# AE_ESP_mnt_board.net
KiCad netlist of a schematic drawn in EAGLE
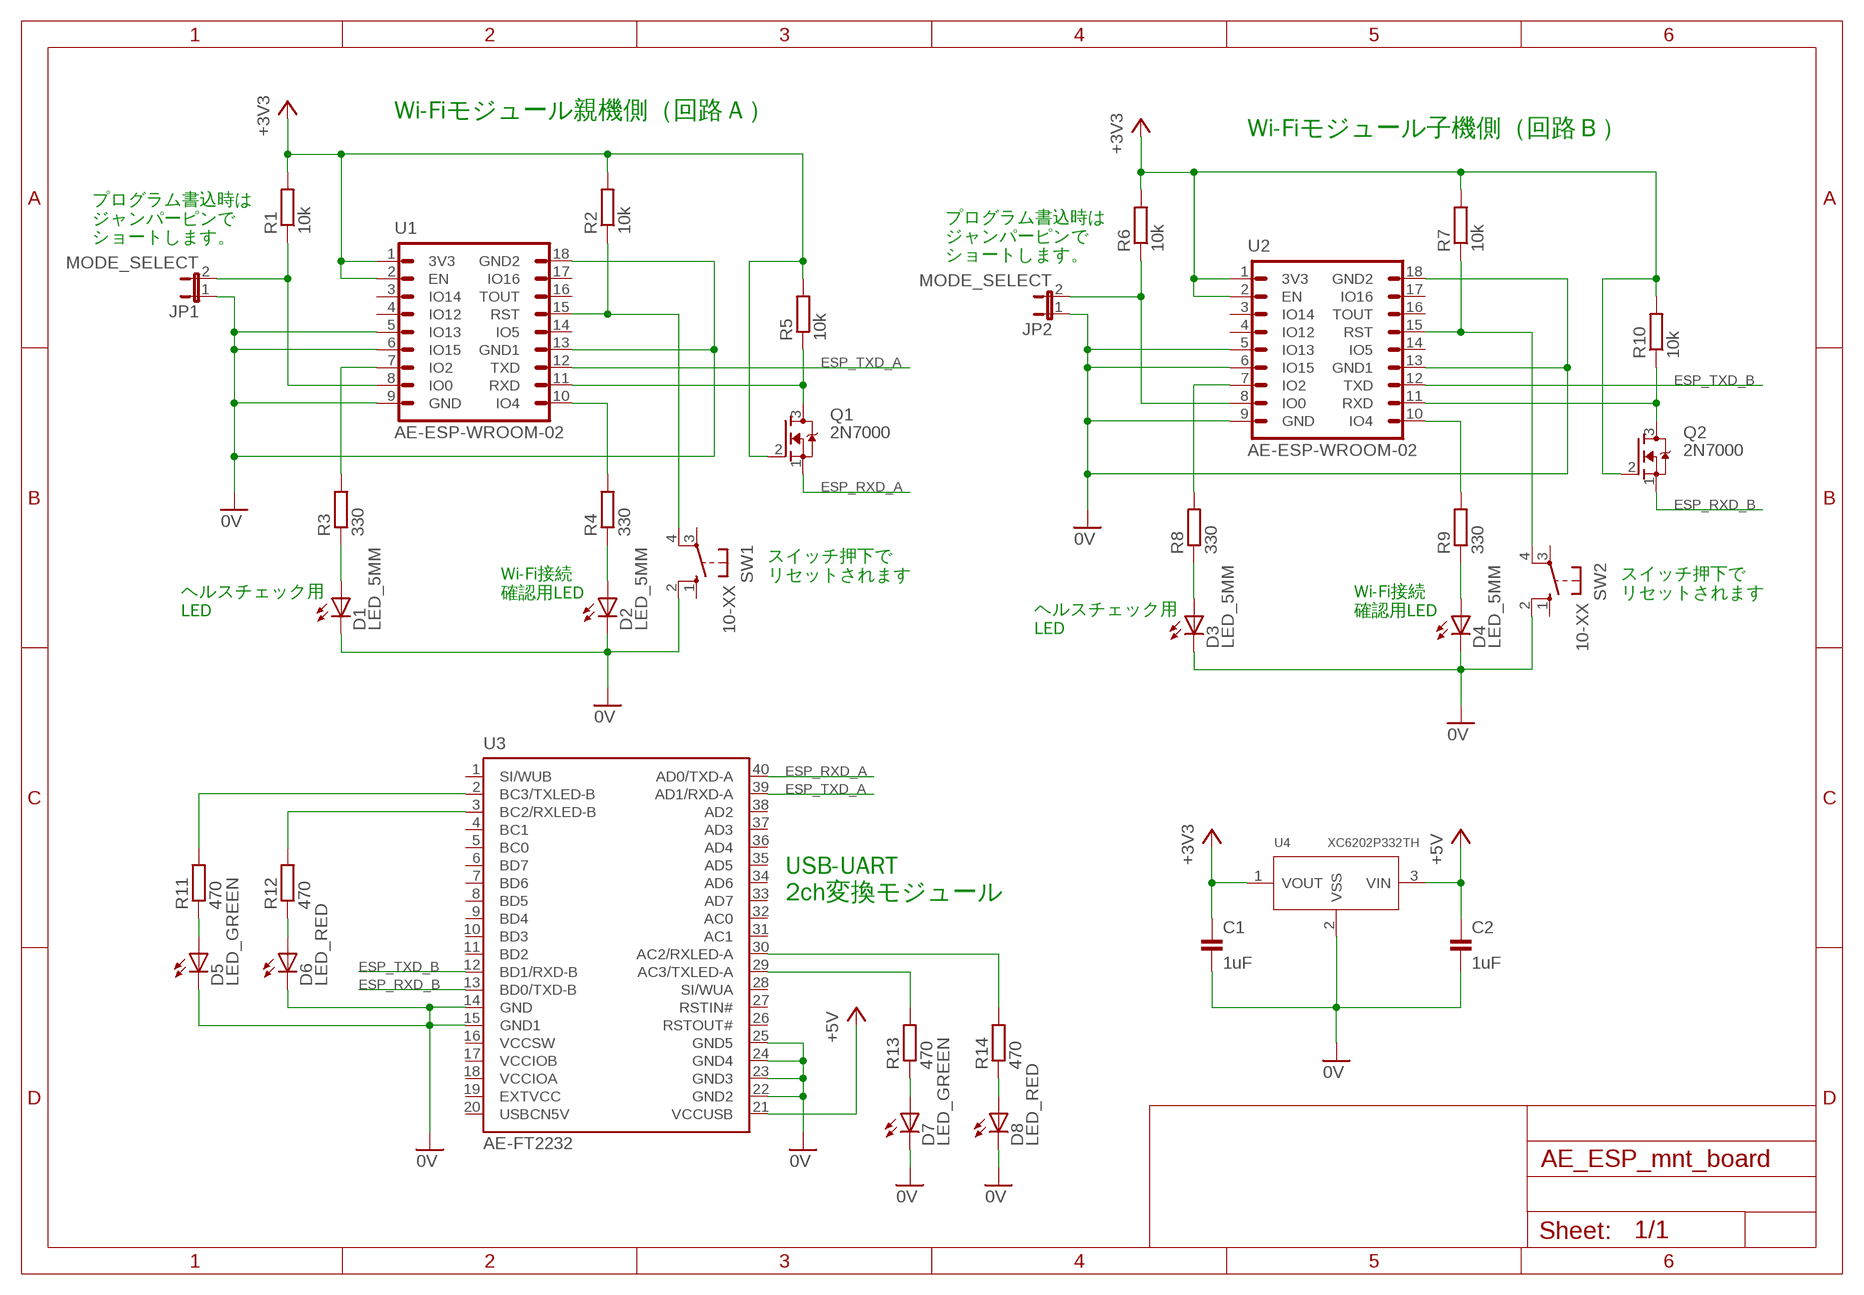
[diagram p0: schematic, sheet 1]

(export (version "E")
  (design (tool "Eeschema 10.0.6"))
  (components
    (comp (ref "C1")
      (value "1uF")
      (footprint "eagle-import:CAP_200MIL")
      (libsource (lib "eagle-import") (part "CAP_200MIL"))
    )
    (comp (ref "C2")
      (value "1uF")
      (footprint "eagle-import:CAP_200MIL")
      (libsource (lib "eagle-import") (part "CAP_200MIL"))
    )
    (comp (ref "D1")
      (value "LED_5MM")
      (footprint "eagle-import:LED5MM")
      (libsource (lib "eagle-import") (part "LED_5MM"))
    )
    (comp (ref "D2")
      (value "LED_5MM")
      (footprint "eagle-import:LED5MM")
      (libsource (lib "eagle-import") (part "LED_5MM"))
    )
    (comp (ref "D3")
      (value "LED_5MM")
      (footprint "eagle-import:LED5MM")
      (libsource (lib "eagle-import") (part "LED_5MM"))
    )
    (comp (ref "D4")
      (value "LED_5MM")
      (footprint "eagle-import:LED5MM")
      (libsource (lib "eagle-import") (part "LED_5MM"))
    )
    (comp (ref "D5")
      (value "LED_GREEN")
      (footprint "eagle-import:LED5MM")
      (libsource (lib "eagle-import") (part "LED_5MM"))
    )
    (comp (ref "D6")
      (value "LED_RED")
      (footprint "eagle-import:LED5MM")
      (libsource (lib "eagle-import") (part "LED_5MM"))
    )
    (comp (ref "D7")
      (value "LED_GREEN")
      (footprint "eagle-import:LED5MM")
      (libsource (lib "eagle-import") (part "LED_5MM"))
    )
    (comp (ref "D8")
      (value "LED_RED")
      (footprint "eagle-import:LED5MM")
      (libsource (lib "eagle-import") (part "LED_5MM"))
    )
    (comp (ref "JP1")
      (value "MODE_SELECT")
      (footprint "eagle-import:JP1")
      (libsource (lib "eagle-import") (part "JP1E"))
    )
    (comp (ref "JP2")
      (value "MODE_SELECT")
      (footprint "eagle-import:JP1")
      (libsource (lib "eagle-import") (part "JP1E"))
    )
    (comp (ref "Q1")
      (value "2N7000")
      (footprint "eagle-import:TO-92NL")
      (libsource (lib "eagle-import") (part "2N7000"))
    )
    (comp (ref "Q2")
      (value "2N7000")
      (footprint "eagle-import:TO-92NL")
      (libsource (lib "eagle-import") (part "2N7000"))
    )
    (comp (ref "R1")
      (value "10k")
      (footprint "eagle-import:RESISTOR_0207_300MIL")
      (libsource (lib "eagle-import") (part "RESISTOR_300MIL"))
    )
    (comp (ref "R2")
      (value "10k")
      (footprint "eagle-import:RESISTOR_0207_300MIL")
      (libsource (lib "eagle-import") (part "RESISTOR_300MIL"))
    )
    (comp (ref "R3")
      (value "330")
      (footprint "eagle-import:RESISTOR_0207_300MIL")
      (libsource (lib "eagle-import") (part "RESISTOR_300MIL"))
    )
    (comp (ref "R4")
      (value "330")
      (footprint "eagle-import:RESISTOR_0207_300MIL")
      (libsource (lib "eagle-import") (part "RESISTOR_300MIL"))
    )
    (comp (ref "R5")
      (value "10k")
      (footprint "eagle-import:RESISTOR_0207_300MIL")
      (libsource (lib "eagle-import") (part "RESISTOR_300MIL"))
    )
    (comp (ref "R6")
      (value "10k")
      (footprint "eagle-import:RESISTOR_0207_300MIL")
      (libsource (lib "eagle-import") (part "RESISTOR_300MIL"))
    )
    (comp (ref "R7")
      (value "10k")
      (footprint "eagle-import:RESISTOR_0207_300MIL")
      (libsource (lib "eagle-import") (part "RESISTOR_300MIL"))
    )
    (comp (ref "R8")
      (value "330")
      (footprint "eagle-import:RESISTOR_0207_300MIL")
      (libsource (lib "eagle-import") (part "RESISTOR_300MIL"))
    )
    (comp (ref "R9")
      (value "330")
      (footprint "eagle-import:RESISTOR_0207_300MIL")
      (libsource (lib "eagle-import") (part "RESISTOR_300MIL"))
    )
    (comp (ref "R10")
      (value "10k")
      (footprint "eagle-import:RESISTOR_0207_300MIL")
      (libsource (lib "eagle-import") (part "RESISTOR_300MIL"))
    )
    (comp (ref "R11")
      (value "470")
      (footprint "eagle-import:RESISTOR_0207_300MIL")
      (libsource (lib "eagle-import") (part "RESISTOR_300MIL"))
    )
    (comp (ref "R12")
      (value "470")
      (footprint "eagle-import:RESISTOR_0207_300MIL")
      (libsource (lib "eagle-import") (part "RESISTOR_300MIL"))
    )
    (comp (ref "R13")
      (value "470")
      (footprint "eagle-import:RESISTOR_0207_300MIL")
      (libsource (lib "eagle-import") (part "RESISTOR_300MIL"))
    )
    (comp (ref "R14")
      (value "470")
      (footprint "eagle-import:RESISTOR_0207_300MIL")
      (libsource (lib "eagle-import") (part "RESISTOR_300MIL"))
    )
    (comp (ref "SW1")
      (value "10-XX")
      (footprint "eagle-import:B3F-10XX")
      (libsource (lib "eagle-import") (part "10-XX"))
    )
    (comp (ref "SW2")
      (value "10-XX")
      (footprint "eagle-import:B3F-10XX")
      (libsource (lib "eagle-import") (part "10-XX"))
    )
    (comp (ref "U1")
      (value "AE-ESP-WROOM-02")
      (footprint "eagle-import:DIL18_AE-ESP-WROOM-02")
      (libsource (lib "eagle-import") (part "AE-ESP-WROOM-02"))
    )
    (comp (ref "U2")
      (value "AE-ESP-WROOM-02")
      (footprint "eagle-import:DIL18_AE-ESP-WROOM-02")
      (libsource (lib "eagle-import") (part "AE-ESP-WROOM-02"))
    )
    (comp (ref "U3")
      (value "AE-FT2232")
      (footprint "eagle-import:DIL40")
      (libsource (lib "eagle-import") (part "AE-FT2232"))
    )
    (comp (ref "U4")
      (value "XC6202P332TH")
      (footprint "eagle-import:TO92-LINE")
      (libsource (lib "eagle-import") (part "XC6202P332TH"))
    )
  )
  (nets
    (net (code "1") (name "+3V3") (class "Default")
      (node (ref "C1") (pin "1") (pinfunction "1_1") (pintype "passive"))
      (node (ref "Q1") (pin "2") (pinfunction "G_2") (pintype "passive"))
      (node (ref "Q2") (pin "2") (pinfunction "G_2") (pintype "passive"))
      (node (ref "R1") (pin "2") (pinfunction "2_2") (pintype "passive"))
      (node (ref "R10") (pin "2") (pinfunction "2_2") (pintype "passive"))
      (node (ref "R2") (pin "2") (pinfunction "2_2") (pintype "passive"))
      (node (ref "R5") (pin "2") (pinfunction "2_2") (pintype "passive"))
      (node (ref "R6") (pin "2") (pinfunction "2_2") (pintype "passive"))
      (node (ref "R7") (pin "2") (pinfunction "2_2") (pintype "passive"))
      (node (ref "U1") (pin "1") (pinfunction "3V3_1") (pintype "passive"))
      (node (ref "U1") (pin "2") (pinfunction "EN_2") (pintype "bidirectional"))
      (node (ref "U2") (pin "1") (pinfunction "3V3_1") (pintype "passive"))
      (node (ref "U2") (pin "2") (pinfunction "EN_2") (pintype "bidirectional"))
      (node (ref "U4") (pin "1") (pinfunction "VOUT_1") (pintype "passive"))
    )
    (net (code "2") (name "+5V") (class "Default")
      (node (ref "C2") (pin "1") (pinfunction "1_1") (pintype "passive"))
      (node (ref "U3") (pin "21") (pinfunction "VCCUSB_21") (pintype "passive"))
      (node (ref "U4") (pin "3") (pinfunction "VIN_3") (pintype "passive"))
    )
    (net (code "3") (name "/ESP_RXD_A") (class "Default")
      (node (ref "Q1") (pin "1") (pinfunction "S_1") (pintype "passive"))
      (node (ref "U3") (pin "40") (pinfunction "AD0/TXD-A_40") (pintype "bidirectional"))
    )
    (net (code "4") (name "/ESP_RXD_B") (class "Default")
      (node (ref "Q2") (pin "1") (pinfunction "S_1") (pintype "passive"))
      (node (ref "U3") (pin "13") (pinfunction "BD0/TXD-B_13") (pintype "bidirectional"))
    )
    (net (code "5") (name "/ESP_TXD_A") (class "Default")
      (node (ref "U1") (pin "12") (pinfunction "TXD_12") (pintype "bidirectional"))
      (node (ref "U3") (pin "39") (pinfunction "AD1/RXD-A_39") (pintype "bidirectional"))
    )
    (net (code "6") (name "/ESP_TXD_B") (class "Default")
      (node (ref "U2") (pin "12") (pinfunction "TXD_12") (pintype "bidirectional"))
      (node (ref "U3") (pin "12") (pinfunction "BD1/RXD-B_12") (pintype "bidirectional"))
    )
    (net (code "7") (name "0V") (class "Default")
      (node (ref "C1") (pin "2") (pinfunction "2_2") (pintype "passive"))
      (node (ref "C2") (pin "2") (pinfunction "2_2") (pintype "passive"))
      (node (ref "D1") (pin "K") (pinfunction "C_K") (pintype "passive"))
      (node (ref "D2") (pin "K") (pinfunction "C_K") (pintype "passive"))
      (node (ref "D3") (pin "K") (pinfunction "C_K") (pintype "passive"))
      (node (ref "D4") (pin "K") (pinfunction "C_K") (pintype "passive"))
      (node (ref "D5") (pin "K") (pinfunction "C_K") (pintype "passive"))
      (node (ref "D6") (pin "K") (pinfunction "C_K") (pintype "passive"))
      (node (ref "D7") (pin "K") (pinfunction "C_K") (pintype "passive"))
      (node (ref "D8") (pin "K") (pinfunction "C_K") (pintype "passive"))
      (node (ref "JP1") (pin "1") (pinfunction "1_1") (pintype "passive"))
      (node (ref "JP2") (pin "1") (pinfunction "1_1") (pintype "passive"))
      (node (ref "SW1") (pin "2") (pinfunction "S1_2") (pintype "passive"))
      (node (ref "SW2") (pin "2") (pinfunction "S1_2") (pintype "passive"))
      (node (ref "U1") (pin "13") (pinfunction "GND1_13") (pintype "passive"))
      (node (ref "U1") (pin "18") (pinfunction "GND2_18") (pintype "passive"))
      (node (ref "U1") (pin "5") (pinfunction "IO13_5") (pintype "bidirectional"))
      (node (ref "U1") (pin "6") (pinfunction "IO15_6") (pintype "bidirectional"))
      (node (ref "U1") (pin "9") (pinfunction "GND_9") (pintype "passive"))
      (node (ref "U2") (pin "13") (pinfunction "GND1_13") (pintype "passive"))
      (node (ref "U2") (pin "18") (pinfunction "GND2_18") (pintype "passive"))
      (node (ref "U2") (pin "5") (pinfunction "IO13_5") (pintype "bidirectional"))
      (node (ref "U2") (pin "6") (pinfunction "IO15_6") (pintype "bidirectional"))
      (node (ref "U2") (pin "9") (pinfunction "GND_9") (pintype "passive"))
      (node (ref "U3") (pin "14") (pinfunction "GND_14") (pintype "passive"))
      (node (ref "U3") (pin "15") (pinfunction "GND1_15") (pintype "passive"))
      (node (ref "U3") (pin "22") (pinfunction "GND2_22") (pintype "passive"))
      (node (ref "U3") (pin "23") (pinfunction "GND3_23") (pintype "passive"))
      (node (ref "U3") (pin "24") (pinfunction "GND4_24") (pintype "passive"))
      (node (ref "U3") (pin "25") (pinfunction "GND5_25") (pintype "passive"))
      (node (ref "U4") (pin "2") (pinfunction "VSS_2") (pintype "passive"))
    )
    (net (code "8") (name "Net-(D1-PadA)") (class "Default")
      (node (ref "D1") (pin "A") (pinfunction "A_A") (pintype "passive"))
      (node (ref "R3") (pin "1") (pinfunction "1_1") (pintype "passive"))
    )
    (net (code "9") (name "Net-(D2-PadA)") (class "Default")
      (node (ref "D2") (pin "A") (pinfunction "A_A") (pintype "passive"))
      (node (ref "R4") (pin "1") (pinfunction "1_1") (pintype "passive"))
    )
    (net (code "10") (name "Net-(D3-PadA)") (class "Default")
      (node (ref "D3") (pin "A") (pinfunction "A_A") (pintype "passive"))
      (node (ref "R8") (pin "1") (pinfunction "1_1") (pintype "passive"))
    )
    (net (code "11") (name "Net-(D4-PadA)") (class "Default")
      (node (ref "D4") (pin "A") (pinfunction "A_A") (pintype "passive"))
      (node (ref "R9") (pin "1") (pinfunction "1_1") (pintype "passive"))
    )
    (net (code "12") (name "Net-(D5-PadA)") (class "Default")
      (node (ref "D5") (pin "A") (pinfunction "A_A") (pintype "passive"))
      (node (ref "R11") (pin "1") (pinfunction "1_1") (pintype "passive"))
    )
    (net (code "13") (name "Net-(D6-PadA)") (class "Default")
      (node (ref "D6") (pin "A") (pinfunction "A_A") (pintype "passive"))
      (node (ref "R12") (pin "1") (pinfunction "1_1") (pintype "passive"))
    )
    (net (code "14") (name "Net-(D7-PadA)") (class "Default")
      (node (ref "D7") (pin "A") (pinfunction "A_A") (pintype "passive"))
      (node (ref "R13") (pin "1") (pinfunction "1_1") (pintype "passive"))
    )
    (net (code "15") (name "Net-(D8-PadA)") (class "Default")
      (node (ref "D8") (pin "A") (pinfunction "A_A") (pintype "passive"))
      (node (ref "R14") (pin "1") (pinfunction "1_1") (pintype "passive"))
    )
    (net (code "16") (name "Net-(Q1-D)") (class "Default")
      (node (ref "Q1") (pin "3") (pinfunction "D_3") (pintype "passive"))
      (node (ref "R5") (pin "1") (pinfunction "1_1") (pintype "passive"))
      (node (ref "U1") (pin "11") (pinfunction "RXD_11") (pintype "bidirectional"))
    )
    (net (code "17") (name "Net-(Q2-D)") (class "Default")
      (node (ref "Q2") (pin "3") (pinfunction "D_3") (pintype "passive"))
      (node (ref "R10") (pin "1") (pinfunction "1_1") (pintype "passive"))
      (node (ref "U2") (pin "11") (pinfunction "RXD_11") (pintype "bidirectional"))
    )
    (net (code "18") (name "Net-(SW1-P1)") (class "Default")
      (node (ref "R2") (pin "1") (pinfunction "1_1") (pintype "passive"))
      (node (ref "SW1") (pin "4") (pinfunction "P1_4") (pintype "passive"))
      (node (ref "U1") (pin "15") (pinfunction "RST_15") (pintype "bidirectional"))
    )
    (net (code "19") (name "Net-(SW2-P1)") (class "Default")
      (node (ref "R7") (pin "1") (pinfunction "1_1") (pintype "passive"))
      (node (ref "SW2") (pin "4") (pinfunction "P1_4") (pintype "passive"))
      (node (ref "U2") (pin "15") (pinfunction "RST_15") (pintype "bidirectional"))
    )
    (net (code "20") (name "Net-(U1-IO0)") (class "Default")
      (node (ref "JP1") (pin "2") (pinfunction "2_2") (pintype "passive"))
      (node (ref "R1") (pin "1") (pinfunction "1_1") (pintype "passive"))
      (node (ref "U1") (pin "8") (pinfunction "IO0_8") (pintype "bidirectional"))
    )
    (net (code "21") (name "Net-(U1-IO2)") (class "Default")
      (node (ref "R3") (pin "2") (pinfunction "2_2") (pintype "passive"))
      (node (ref "U1") (pin "7") (pinfunction "IO2_7") (pintype "bidirectional"))
    )
    (net (code "22") (name "Net-(U1-IO4)") (class "Default")
      (node (ref "R4") (pin "2") (pinfunction "2_2") (pintype "passive"))
      (node (ref "U1") (pin "10") (pinfunction "IO4_10") (pintype "bidirectional"))
    )
    (net (code "23") (name "Net-(U2-IO0)") (class "Default")
      (node (ref "JP2") (pin "2") (pinfunction "2_2") (pintype "passive"))
      (node (ref "R6") (pin "1") (pinfunction "1_1") (pintype "passive"))
      (node (ref "U2") (pin "8") (pinfunction "IO0_8") (pintype "bidirectional"))
    )
    (net (code "24") (name "Net-(U2-IO2)") (class "Default")
      (node (ref "R8") (pin "2") (pinfunction "2_2") (pintype "passive"))
      (node (ref "U2") (pin "7") (pinfunction "IO2_7") (pintype "bidirectional"))
    )
    (net (code "25") (name "Net-(U2-IO4)") (class "Default")
      (node (ref "R9") (pin "2") (pinfunction "2_2") (pintype "passive"))
      (node (ref "U2") (pin "10") (pinfunction "IO4_10") (pintype "bidirectional"))
    )
    (net (code "26") (name "Net-(U3-AC2{slash}RXLED-A)") (class "Default")
      (node (ref "R14") (pin "2") (pinfunction "2_2") (pintype "passive"))
      (node (ref "U3") (pin "30") (pinfunction "AC2/RXLED-A_30") (pintype "bidirectional"))
    )
    (net (code "27") (name "Net-(U3-AC3{slash}TXLED-A)") (class "Default")
      (node (ref "R13") (pin "2") (pinfunction "2_2") (pintype "passive"))
      (node (ref "U3") (pin "29") (pinfunction "AC3/TXLED-A_29") (pintype "bidirectional"))
    )
    (net (code "28") (name "Net-(U3-BC2{slash}RXLED-B)") (class "Default")
      (node (ref "R12") (pin "2") (pinfunction "2_2") (pintype "passive"))
      (node (ref "U3") (pin "3") (pinfunction "BC2/RXLED-B_3") (pintype "bidirectional"))
    )
    (net (code "29") (name "Net-(U3-BC3{slash}TXLED-B)") (class "Default")
      (node (ref "R11") (pin "2") (pinfunction "2_2") (pintype "passive"))
      (node (ref "U3") (pin "2") (pinfunction "BC3/TXLED-B_2") (pintype "bidirectional"))
    )
    (net (code "30") (name "unconnected-(SW1-P-Pad3)") (class "Default")
      (node (ref "SW1") (pin "3") (pinfunction "P_3") (pintype "passive"))
    )
    (net (code "31") (name "unconnected-(SW1-S-Pad1)") (class "Default")
      (node (ref "SW1") (pin "1") (pinfunction "S_1") (pintype "passive"))
    )
    (net (code "32") (name "unconnected-(SW2-P-Pad3)") (class "Default")
      (node (ref "SW2") (pin "3") (pinfunction "P_3") (pintype "passive"))
    )
    (net (code "33") (name "unconnected-(SW2-S-Pad1)") (class "Default")
      (node (ref "SW2") (pin "1") (pinfunction "S_1") (pintype "passive"))
    )
    (net (code "34") (name "unconnected-(U1-IO5-Pad14)") (class "Default")
      (node (ref "U1") (pin "14") (pinfunction "IO5_14") (pintype "bidirectional"))
    )
    (net (code "35") (name "unconnected-(U1-IO12-Pad4)") (class "Default")
      (node (ref "U1") (pin "4") (pinfunction "IO12_4") (pintype "bidirectional"))
    )
    (net (code "36") (name "unconnected-(U1-IO14-Pad3)") (class "Default")
      (node (ref "U1") (pin "3") (pinfunction "IO14_3") (pintype "bidirectional"))
    )
    (net (code "37") (name "unconnected-(U1-IO16-Pad17)") (class "Default")
      (node (ref "U1") (pin "17") (pinfunction "IO16_17") (pintype "bidirectional"))
    )
    (net (code "38") (name "unconnected-(U1-TOUT-Pad16)") (class "Default")
      (node (ref "U1") (pin "16") (pinfunction "TOUT_16") (pintype "bidirectional"))
    )
    (net (code "39") (name "unconnected-(U2-IO5-Pad14)") (class "Default")
      (node (ref "U2") (pin "14") (pinfunction "IO5_14") (pintype "bidirectional"))
    )
    (net (code "40") (name "unconnected-(U2-IO12-Pad4)") (class "Default")
      (node (ref "U2") (pin "4") (pinfunction "IO12_4") (pintype "bidirectional"))
    )
    (net (code "41") (name "unconnected-(U2-IO14-Pad3)") (class "Default")
      (node (ref "U2") (pin "3") (pinfunction "IO14_3") (pintype "bidirectional"))
    )
    (net (code "42") (name "unconnected-(U2-IO16-Pad17)") (class "Default")
      (node (ref "U2") (pin "17") (pinfunction "IO16_17") (pintype "bidirectional"))
    )
    (net (code "43") (name "unconnected-(U2-TOUT-Pad16)") (class "Default")
      (node (ref "U2") (pin "16") (pinfunction "TOUT_16") (pintype "bidirectional"))
    )
    (net (code "44") (name "unconnected-(U3-AC0-Pad32)") (class "Default")
      (node (ref "U3") (pin "32") (pinfunction "AC0_32") (pintype "bidirectional"))
    )
    (net (code "45") (name "unconnected-(U3-AC1-Pad31)") (class "Default")
      (node (ref "U3") (pin "31") (pinfunction "AC1_31") (pintype "bidirectional"))
    )
    (net (code "46") (name "unconnected-(U3-AD2-Pad38)") (class "Default")
      (node (ref "U3") (pin "38") (pinfunction "AD2_38") (pintype "bidirectional"))
    )
    (net (code "47") (name "unconnected-(U3-AD3-Pad37)") (class "Default")
      (node (ref "U3") (pin "37") (pinfunction "AD3_37") (pintype "bidirectional"))
    )
    (net (code "48") (name "unconnected-(U3-AD4-Pad36)") (class "Default")
      (node (ref "U3") (pin "36") (pinfunction "AD4_36") (pintype "bidirectional"))
    )
    (net (code "49") (name "unconnected-(U3-AD5-Pad35)") (class "Default")
      (node (ref "U3") (pin "35") (pinfunction "AD5_35") (pintype "bidirectional"))
    )
    (net (code "50") (name "unconnected-(U3-AD6-Pad34)") (class "Default")
      (node (ref "U3") (pin "34") (pinfunction "AD6_34") (pintype "bidirectional"))
    )
    (net (code "51") (name "unconnected-(U3-AD7-Pad33)") (class "Default")
      (node (ref "U3") (pin "33") (pinfunction "AD7_33") (pintype "bidirectional"))
    )
    (net (code "52") (name "unconnected-(U3-BC0-Pad5)") (class "Default")
      (node (ref "U3") (pin "5") (pinfunction "BC0_5") (pintype "bidirectional"))
    )
    (net (code "53") (name "unconnected-(U3-BC1-Pad4)") (class "Default")
      (node (ref "U3") (pin "4") (pinfunction "BC1_4") (pintype "bidirectional"))
    )
    (net (code "54") (name "unconnected-(U3-BD2-Pad11)") (class "Default")
      (node (ref "U3") (pin "11") (pinfunction "BD2_11") (pintype "bidirectional"))
    )
    (net (code "55") (name "unconnected-(U3-BD3-Pad10)") (class "Default")
      (node (ref "U3") (pin "10") (pinfunction "BD3_10") (pintype "bidirectional"))
    )
    (net (code "56") (name "unconnected-(U3-BD4-Pad9)") (class "Default")
      (node (ref "U3") (pin "9") (pinfunction "BD4_9") (pintype "bidirectional"))
    )
    (net (code "57") (name "unconnected-(U3-BD5-Pad8)") (class "Default")
      (node (ref "U3") (pin "8") (pinfunction "BD5_8") (pintype "bidirectional"))
    )
    (net (code "58") (name "unconnected-(U3-BD6-Pad7)") (class "Default")
      (node (ref "U3") (pin "7") (pinfunction "BD6_7") (pintype "bidirectional"))
    )
    (net (code "59") (name "unconnected-(U3-BD7-Pad6)") (class "Default")
      (node (ref "U3") (pin "6") (pinfunction "BD7_6") (pintype "bidirectional"))
    )
    (net (code "60") (name "unconnected-(U3-EXTVCC-Pad19)") (class "Default")
      (node (ref "U3") (pin "19") (pinfunction "EXTVCC_19") (pintype "passive"))
    )
    (net (code "61") (name "unconnected-(U3-RSTIN#-Pad27)") (class "Default")
      (node (ref "U3") (pin "27") (pinfunction "RSTIN#_27") (pintype "bidirectional"))
    )
    (net (code "62") (name "unconnected-(U3-RSTOUT#-Pad26)") (class "Default")
      (node (ref "U3") (pin "26") (pinfunction "RSTOUT#_26") (pintype "bidirectional"))
    )
    (net (code "63") (name "unconnected-(U3-SI{slash}WUA-Pad28)") (class "Default")
      (node (ref "U3") (pin "28") (pinfunction "SI/WUA_28") (pintype "bidirectional"))
    )
    (net (code "64") (name "unconnected-(U3-SI{slash}WUB-Pad1)") (class "Default")
      (node (ref "U3") (pin "1") (pinfunction "SI/WUB_1") (pintype "bidirectional"))
    )
    (net (code "65") (name "unconnected-(U3-USBCN5V-Pad20)") (class "Default")
      (node (ref "U3") (pin "20") (pinfunction "USBCN5V_20") (pintype "passive"))
    )
    (net (code "66") (name "unconnected-(U3-VCCIOA-Pad18)") (class "Default")
      (node (ref "U3") (pin "18") (pinfunction "VCCIOA_18") (pintype "passive"))
    )
    (net (code "67") (name "unconnected-(U3-VCCIOB-Pad17)") (class "Default")
      (node (ref "U3") (pin "17") (pinfunction "VCCIOB_17") (pintype "passive"))
    )
    (net (code "68") (name "unconnected-(U3-VCCSW-Pad16)") (class "Default")
      (node (ref "U3") (pin "16") (pinfunction "VCCSW_16") (pintype "passive"))
    )
  )
)
